# Sound_Activation_2019-2.net
KiCad netlist of a schematic drawn in EAGLE
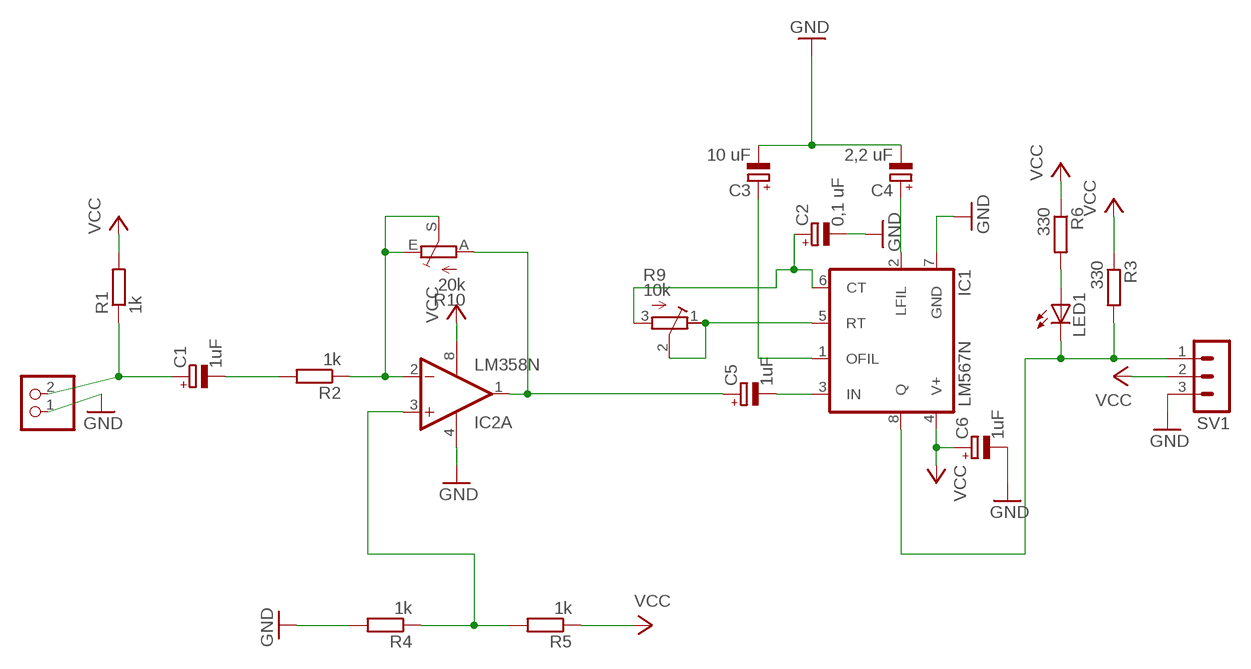
[diagram p0: schematic, sheet 1]

(export (version "E")
  (design (tool "Eeschema 10.0.6"))
  (components
    (comp (ref "C1")
      (value "1uF")
      (footprint "eagle-import:E1,8-4")
      (libsource (lib "eagle-import") (part "CPOL-EUE1.8-4"))
    )
    (comp (ref "C2")
      (value "0,1 uF")
      (footprint "eagle-import:E1,8-4")
      (libsource (lib "eagle-import") (part "CPOL-EUE1.8-4"))
    )
    (comp (ref "C3")
      (value "10 uF")
      (footprint "eagle-import:E1,8-4")
      (libsource (lib "eagle-import") (part "CPOL-EUE1.8-4"))
    )
    (comp (ref "C4")
      (value "2,2 uF")
      (footprint "eagle-import:E1,8-4")
      (libsource (lib "eagle-import") (part "CPOL-EUE1.8-4"))
    )
    (comp (ref "C5")
      (value "1uF")
      (footprint "eagle-import:E1,8-4")
      (libsource (lib "eagle-import") (part "CPOL-EUE1.8-4"))
    )
    (comp (ref "C6")
      (value "1uF")
      (footprint "eagle-import:E1,8-4")
      (libsource (lib "eagle-import") (part "CPOL-EUE1.8-4"))
    )
    (comp (ref "IC1")
      (value "LM567N")
      (footprint "eagle-import:DIL08")
      (libsource (lib "eagle-import") (part "567NLM"))
    )
    (comp (ref "IC2")
      (value "LM358N")
      (footprint "eagle-import:DIL08")
      (libsource (lib "eagle-import") (part "LM358N"))
    )
    (comp (ref "LED1")
      (value "LED3MM")
      (footprint "eagle-import:LED3MM")
      (libsource (lib "eagle-import") (part "LED3MM"))
    )
    (comp (ref "M1")
      (value "PINHD-1X2")
      (footprint "eagle-import:1X02")
      (libsource (lib "eagle-import") (part "PINHD-1X2"))
    )
    (comp (ref "R1")
      (value "1k")
      (footprint "eagle-import:0204_7")
      (libsource (lib "eagle-import") (part "R-EU_0204/7"))
    )
    (comp (ref "R2")
      (value "1k")
      (footprint "eagle-import:0204_7")
      (libsource (lib "eagle-import") (part "R-EU_0204/7"))
    )
    (comp (ref "R3")
      (value "330")
      (footprint "eagle-import:0204_7")
      (libsource (lib "eagle-import") (part "R-EU_0204/7"))
    )
    (comp (ref "R4")
      (value "1k")
      (footprint "eagle-import:0204_7")
      (libsource (lib "eagle-import") (part "R-EU_0204/7"))
    )
    (comp (ref "R5")
      (value "1k")
      (footprint "eagle-import:0204_7")
      (libsource (lib "eagle-import") (part "R-EU_0204/7"))
    )
    (comp (ref "R6")
      (value "330")
      (footprint "eagle-import:0204_7")
      (libsource (lib "eagle-import") (part "R-EU_0204/7"))
    )
    (comp (ref "R9")
      (value "10k")
      (footprint "eagle-import:RTRIM3006P")
      (libsource (lib "eagle-import") (part "R-TRIMM3006P"))
    )
    (comp (ref "R10")
      (value "20k")
      (footprint "eagle-import:B25P")
      (libsource (lib "eagle-import") (part "TRIM_EU-B25P"))
    )
    (comp (ref "SV1")
      (value "MA03-1")
      (footprint "eagle-import:MA03-1")
      (libsource (lib "eagle-import") (part "MA03-1"))
    )
  )
  (nets
    (net (code "1") (name "GND") (class "Default")
      (node (ref "C2") (pin "-") (pinfunction "-_-") (pintype "passive"))
      (node (ref "C3") (pin "-") (pinfunction "-_-") (pintype "passive"))
      (node (ref "C4") (pin "-") (pinfunction "-_-") (pintype "passive"))
      (node (ref "C6") (pin "-") (pinfunction "-_-") (pintype "passive"))
      (node (ref "IC1") (pin "7") (pinfunction "GND_7") (pintype "power_in"))
      (node (ref "IC2") (pin "4") (pinfunction "V-_4") (pintype "power_in"))
      (node (ref "M1") (pin "1") (pinfunction "1_1") (pintype "passive"))
      (node (ref "R4") (pin "2") (pinfunction "2_2") (pintype "passive"))
      (node (ref "SV1") (pin "3") (pinfunction "3_3") (pintype "passive"))
    )
    (net (code "2") (name "Net-(C1-Pad+)") (class "Default")
      (node (ref "C1") (pin "+") (pinfunction "+_+") (pintype "passive"))
      (node (ref "M1") (pin "2") (pinfunction "2_2") (pintype "passive"))
      (node (ref "R1") (pin "1") (pinfunction "1_1") (pintype "passive"))
    )
    (net (code "3") (name "Net-(C1-Pad-)") (class "Default")
      (node (ref "C1") (pin "-") (pinfunction "-_-") (pintype "passive"))
      (node (ref "R2") (pin "2") (pinfunction "2_2") (pintype "passive"))
    )
    (net (code "4") (name "Net-(IC1-CT)") (class "Default")
      (node (ref "C2") (pin "+") (pinfunction "+_+") (pintype "passive"))
      (node (ref "IC1") (pin "6") (pinfunction "CT_6") (pintype "passive"))
      (node (ref "R9") (pin "3") (pinfunction "A_3") (pintype "passive"))
    )
    (net (code "5") (name "Net-(IC1-IN)") (class "Default")
      (node (ref "C5") (pin "-") (pinfunction "-_-") (pintype "passive"))
      (node (ref "IC1") (pin "3") (pinfunction "IN_3") (pintype "input"))
    )
    (net (code "6") (name "Net-(IC1-LFIL)") (class "Default")
      (node (ref "C4") (pin "+") (pinfunction "+_+") (pintype "passive"))
      (node (ref "IC1") (pin "2") (pinfunction "LFIL_2") (pintype "passive"))
    )
    (net (code "7") (name "Net-(IC1-OFIL)") (class "Default")
      (node (ref "C3") (pin "+") (pinfunction "+_+") (pintype "passive"))
      (node (ref "IC1") (pin "1") (pinfunction "OFIL_1") (pintype "output"))
    )
    (net (code "8") (name "Net-(IC1-Q)") (class "Default")
      (node (ref "IC1") (pin "8") (pinfunction "Q_8") (pintype "output"))
      (node (ref "LED1") (pin "K") (pinfunction "C_K") (pintype "passive"))
      (node (ref "R3") (pin "2") (pinfunction "2_2") (pintype "passive"))
      (node (ref "SV1") (pin "1") (pinfunction "1_1") (pintype "passive"))
    )
    (net (code "9") (name "Net-(IC1-RT)") (class "Default")
      (node (ref "IC1") (pin "5") (pinfunction "RT_5") (pintype "passive"))
      (node (ref "R9") (pin "1") (pinfunction "E_1") (pintype "passive"))
      (node (ref "R9") (pin "2") (pinfunction "S_2") (pintype "passive"))
    )
    (net (code "10") (name "Net-(IC2A-+IN)") (class "Default")
      (node (ref "IC2") (pin "3") (pinfunction "+IN_3") (pintype "input"))
      (node (ref "R4") (pin "1") (pinfunction "1_1") (pintype "passive"))
      (node (ref "R5") (pin "2") (pinfunction "2_2") (pintype "passive"))
    )
    (net (code "11") (name "Net-(IC2A--IN)") (class "Default")
      (node (ref "IC2") (pin "2") (pinfunction "-IN_2") (pintype "input"))
      (node (ref "R10") (pin "E") (pinfunction "E_E") (pintype "passive"))
      (node (ref "R10") (pin "S") (pinfunction "S_S") (pintype "passive"))
      (node (ref "R2") (pin "1") (pinfunction "1_1") (pintype "passive"))
    )
    (net (code "12") (name "Net-(IC2A-OUT)") (class "Default")
      (node (ref "C5") (pin "+") (pinfunction "+_+") (pintype "passive"))
      (node (ref "IC2") (pin "1") (pinfunction "OUT_1") (pintype "output"))
      (node (ref "R10") (pin "A") (pinfunction "A_A") (pintype "passive"))
    )
    (net (code "13") (name "Net-(LED1-PadA)") (class "Default")
      (node (ref "LED1") (pin "A") (pinfunction "A_A") (pintype "passive"))
      (node (ref "R6") (pin "2") (pinfunction "2_2") (pintype "passive"))
    )
    (net (code "14") (name "VCC") (class "Default")
      (node (ref "C6") (pin "+") (pinfunction "+_+") (pintype "passive"))
      (node (ref "IC1") (pin "4") (pinfunction "V+_4") (pintype "power_in"))
      (node (ref "IC2") (pin "8") (pinfunction "V+_8") (pintype "power_in"))
      (node (ref "R1") (pin "2") (pinfunction "2_2") (pintype "passive"))
      (node (ref "R3") (pin "1") (pinfunction "1_1") (pintype "passive"))
      (node (ref "R5") (pin "1") (pinfunction "1_1") (pintype "passive"))
      (node (ref "R6") (pin "1") (pinfunction "1_1") (pintype "passive"))
      (node (ref "SV1") (pin "2") (pinfunction "2_2") (pintype "passive"))
    )
  )
)
